# FULL_CB_PowerSupply_REV_C.net
KiCad netlist of a schematic drawn in Altium Designer
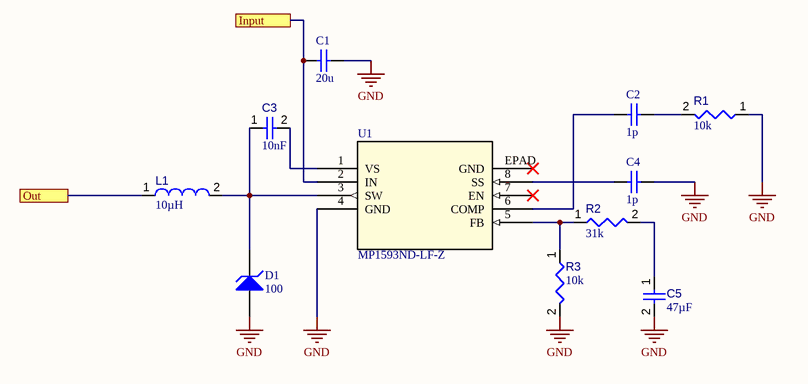
[diagram p0: FULL_CB_PowerSupply_REV_C.SchDoc]

(export (version "E")
  (design (tool "Eeschema 10.0.6"))
  (components
    (comp (ref "C1")
      (value "20u")
      (description "Capacitor")
      (libsource (lib "Simulation Generic Components") (part "Capacitor"))
    )
    (comp (ref "C2")
      (value "1p")
      (description "Capacitor")
      (libsource (lib "Simulation Generic Components") (part "Capacitor"))
    )
    (comp (ref "C3")
      (value "10nF")
      (footprint "CAPC0402(1005)60_L")
      (description "Chip Capacitor, 10nF +/-20%, 50V, 0402, Thickness 0.6 mm")
      (fields (field (name "TOLERANCE") "5%") (field (name "Comment") "Capacitor 10nF +/-20% 50V 0402"))
      (libsource (lib "Universidad Nacional de Colombia") (part "CAP-NP-2"))
    )
    (comp (ref "C4")
      (value "1p")
      (description "Capacitor")
      (libsource (lib "Simulation Generic Components") (part "Capacitor"))
    )
    (comp (ref "C5")
      (value "47µF")
      (footprint "CAPC0805(2012)145_L")
      (description "Chip Capacitor, 47µF +/-40%, 6.3V, 0805, Thickness 1.45 mm")
      (fields (field (name "TOLERANCE") "10%") (field (name "Comment") "Capacitor 47µF +/-40% 6.3V 0805"))
      (libsource (lib "Universidad Nacional de Colombia") (part "CAP-NP-2"))
    )
    (comp (ref "D1")
      (value "Zener Diode")
      (fields (field (name "BV") "100"))
      (libsource (lib "Simulation Generic Components") (part "Zener Diode"))
    )
    (comp (ref "L1")
      (value "10µH")
      (footprint "INDR62-500-1100X850X1100")
      (description "Radial Inductor, 10 uH, +/- 10%, 3 A, -55 to 105 degC, 2-Pin THD, RoHS, Bulk")
      (fields (field (name "TOLERANCE") "10%") (field (name "MANUFACTURER") "Bourns"))
      (libsource (lib "Universidad Nacional de Colombia") (part "IND-2"))
    )
    (comp (ref "R1")
      (value "10k")
      (footprint "RESC1005X40X25ML05T05")
      (description "Chip Resistor, 10 KOhm, +/- 1%, 63 mW, -55 to 155 degC, 0402 (1005 Metric)")
      (fields (field (name "POWER") "63mW") (field (name "TOLERANCE") "1%"))
      (libsource (lib "Universidad Nacional de Colombia") (part "RES-2"))
    )
    (comp (ref "R2")
      (value "31k")
      (footprint "RESC1005X40X25ML05T05")
      (description "Chip Resistor, 10 KOhm, +/- 1%, 63 mW, -55 to 155 degC, 0402 (1005 Metric)")
      (fields (field (name "POWER") "63mW") (field (name "TOLERANCE") "1%"))
      (libsource (lib "Universidad Nacional de Colombia") (part "RES-2"))
    )
    (comp (ref "R3")
      (value "10k")
      (footprint "RESC1005X40X25ML05T05")
      (description "Chip Resistor, 10 KOhm, +/- 1%, 63 mW, -55 to 155 degC, 0402 (1005 Metric)")
      (fields (field (name "POWER") "63mW") (field (name "TOLERANCE") "1%"))
      (libsource (lib "Universidad Nacional de Colombia") (part "RES-2"))
    )
    (comp (ref "U1")
      (value "MP1593ND-LF-Z")
      (footprint "MP1593DN-LF-Z")
      (libsource (lib "Schlib1") (part "Component_1"))
    )
  )
  (nets
    (net (code "1") (name "/Input") (class "Default")
      (node (ref "C1") (pin "1") (pinfunction "1_1") (pintype "passive"))
      (node (ref "U1") (pin "2") (pinfunction "IN_2") (pintype "power_in"))
    )
    (net (code "2") (name "/Out") (class "Default")
      (node (ref "L1") (pin "1") (pinfunction "1_1") (pintype "passive"))
    )
    (net (code "3") (name "GND") (class "Default")
      (node (ref "C1") (pin "2") (pinfunction "2_2") (pintype "passive"))
      (node (ref "C4") (pin "2") (pinfunction "2_2") (pintype "passive"))
      (node (ref "C5") (pin "2") (pinfunction "2_2") (pintype "passive"))
      (node (ref "D1") (pin "1") (pinfunction "A_1") (pintype "passive"))
      (node (ref "R1") (pin "1") (pinfunction "1_1") (pintype "passive"))
      (node (ref "R3") (pin "2") (pinfunction "2_2") (pintype "passive"))
      (node (ref "U1") (pin "4") (pinfunction "GND_4") (pintype "power_in"))
    )
    (net (code "4") (name "Net-(C2-Pad2)") (class "Default")
      (node (ref "C2") (pin "2") (pinfunction "2_2") (pintype "passive"))
      (node (ref "R1") (pin "2") (pinfunction "2_2") (pintype "passive"))
    )
    (net (code "5") (name "Net-(C5-Pad1)") (class "Default")
      (node (ref "C5") (pin "1") (pinfunction "1_1") (pintype "passive"))
      (node (ref "R2") (pin "2") (pinfunction "2_2") (pintype "passive"))
    )
    (net (code "6") (name "Net-(D1-K)") (class "Default")
      (node (ref "C3") (pin "1") (pinfunction "1_1") (pintype "passive"))
      (node (ref "D1") (pin "2") (pinfunction "K_2") (pintype "passive"))
      (node (ref "L1") (pin "2") (pinfunction "2_2") (pintype "passive"))
      (node (ref "U1") (pin "3") (pinfunction "SW_3") (pintype "output"))
    )
    (net (code "7") (name "Net-(U1-COMP)") (class "Default")
      (node (ref "C2") (pin "1") (pinfunction "1_1") (pintype "passive"))
      (node (ref "U1") (pin "6") (pinfunction "COMP_6") (pintype "passive"))
    )
    (net (code "8") (name "Net-(U1-FB)") (class "Default")
      (node (ref "R2") (pin "1") (pinfunction "1_1") (pintype "passive"))
      (node (ref "R3") (pin "1") (pinfunction "1_1") (pintype "passive"))
      (node (ref "U1") (pin "5") (pinfunction "FB_5") (pintype "input"))
    )
    (net (code "9") (name "Net-(U1-SS)") (class "Default")
      (node (ref "C4") (pin "1") (pinfunction "1_1") (pintype "passive"))
      (node (ref "U1") (pin "8") (pinfunction "SS_8") (pintype "input"))
    )
    (net (code "10") (name "Net-(U1-VS)") (class "Default")
      (node (ref "C3") (pin "2") (pinfunction "2_2") (pintype "passive"))
      (node (ref "U1") (pin "1") (pinfunction "VS_1") (pintype "power_in"))
    )
    (net (code "11") (name "unconnected-(U1-EN-Pad7)") (class "Default")
      (node (ref "U1") (pin "7") (pinfunction "EN_7") (pintype "input+no_connect"))
    )
    (net (code "12") (name "unconnected-(U1-GND-PadEPAD)") (class "Default")
      (node (ref "U1") (pin "EPAD") (pinfunction "GND_EPAD") (pintype "power_in+no_connect"))
    )
  )
)
